# digitalLatchShield.net
KiCad netlist of a schematic drawn in EAGLE
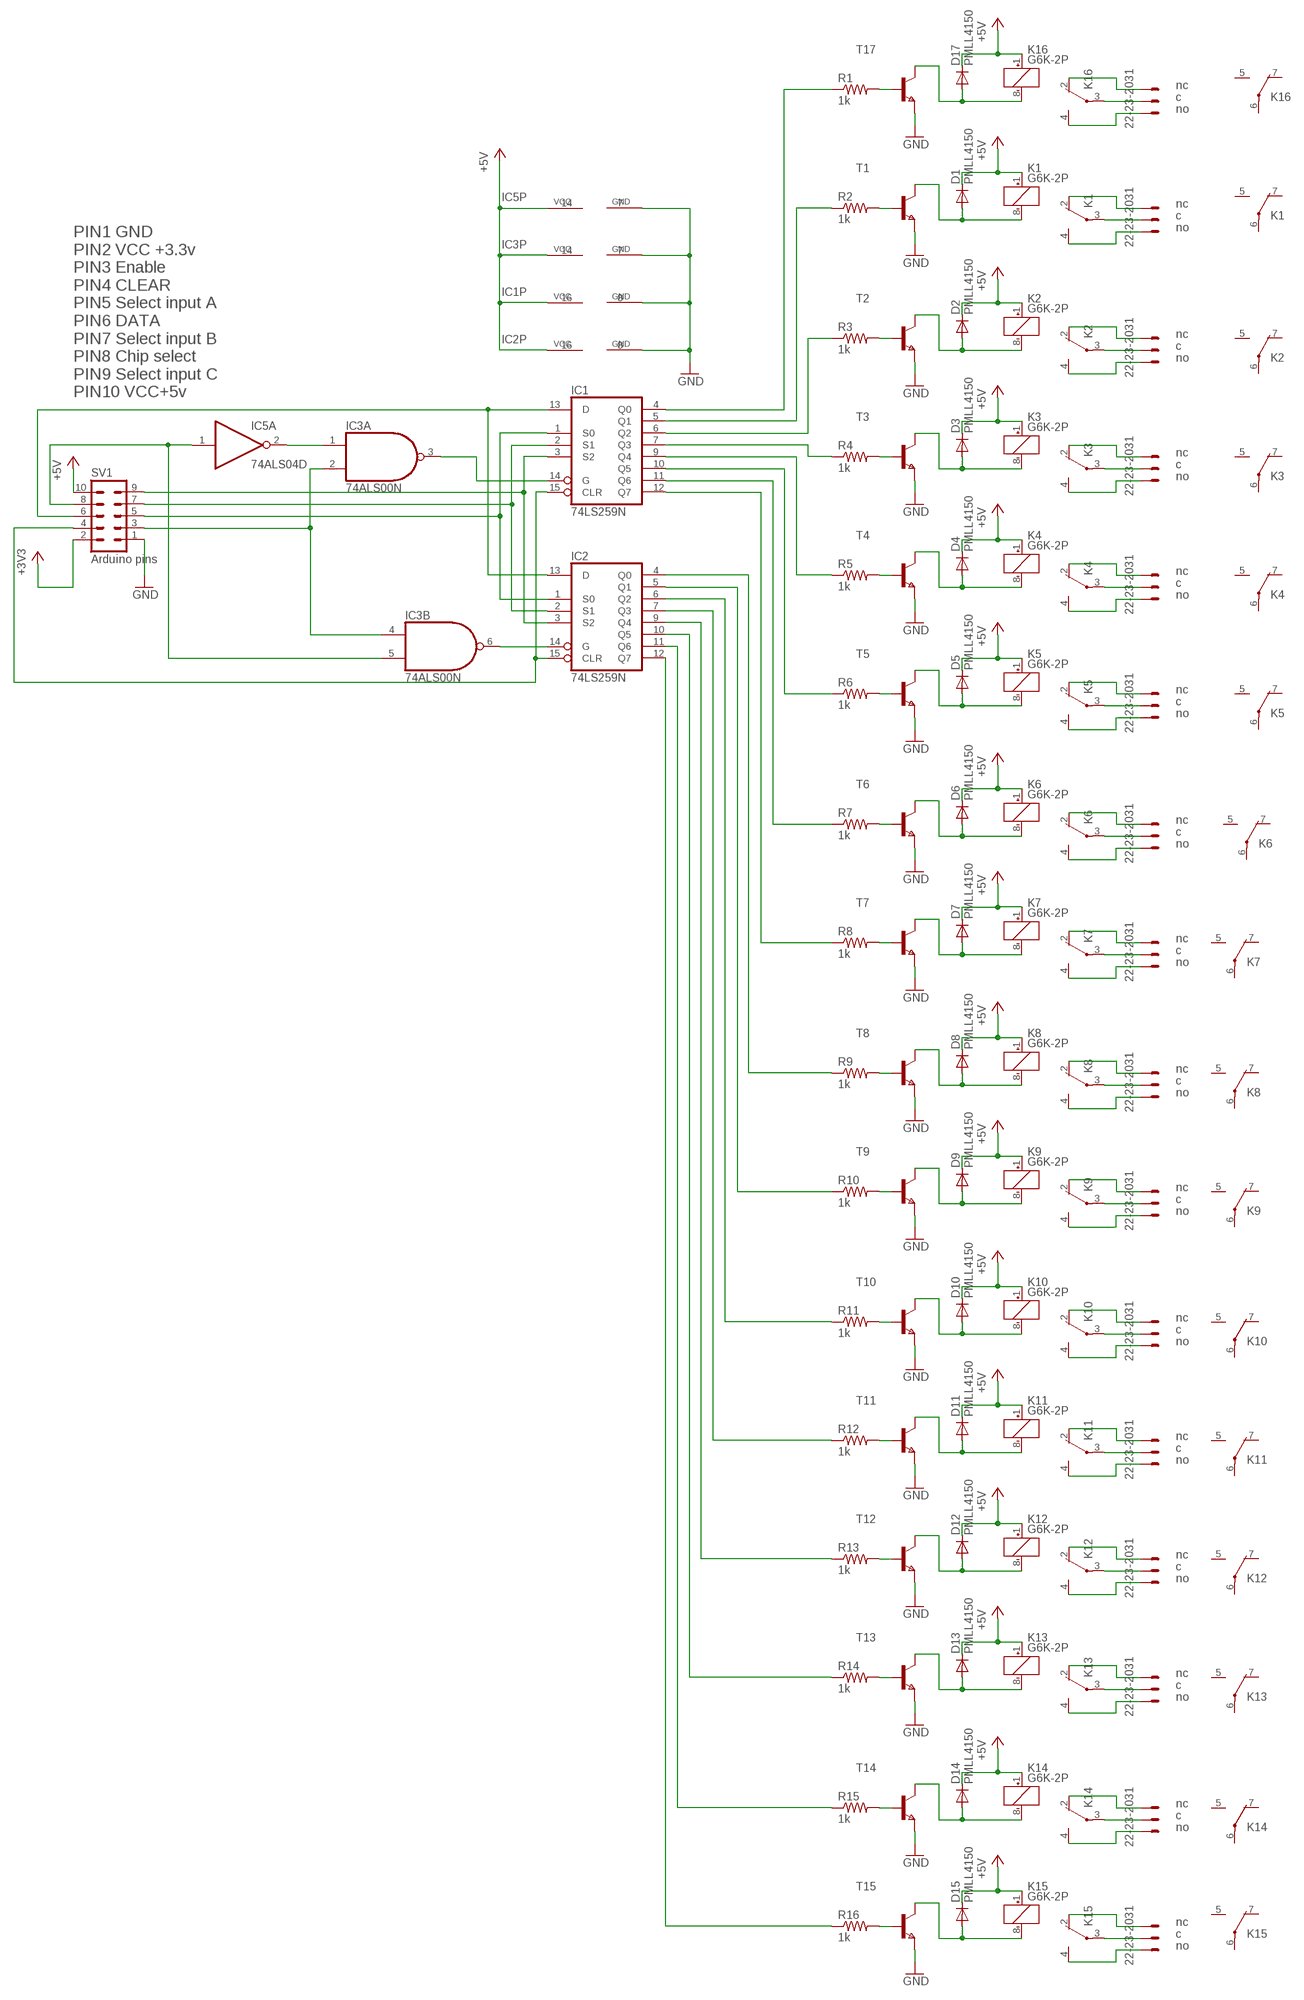
[diagram p0: schematic, sheet 1]

(export (version "E")
  (design (tool "Eeschema 10.0.6"))
  (components
    (comp (ref "D1")
      (value "PMLL4150")
      (footprint "eagle-import:SOD80C")
      (libsource (lib "eagle-import") (part "PMLL4150"))
    )
    (comp (ref "D2")
      (value "PMLL4150")
      (footprint "eagle-import:SOD80C")
      (libsource (lib "eagle-import") (part "PMLL4150"))
    )
    (comp (ref "D3")
      (value "PMLL4150")
      (footprint "eagle-import:SOD80C")
      (libsource (lib "eagle-import") (part "PMLL4150"))
    )
    (comp (ref "D4")
      (value "PMLL4150")
      (footprint "eagle-import:SOD80C")
      (libsource (lib "eagle-import") (part "PMLL4150"))
    )
    (comp (ref "D5")
      (value "PMLL4150")
      (footprint "eagle-import:SOD80C")
      (libsource (lib "eagle-import") (part "PMLL4150"))
    )
    (comp (ref "D6")
      (value "PMLL4150")
      (footprint "eagle-import:SOD80C")
      (libsource (lib "eagle-import") (part "PMLL4150"))
    )
    (comp (ref "D7")
      (value "PMLL4150")
      (footprint "eagle-import:SOD80C")
      (libsource (lib "eagle-import") (part "PMLL4150"))
    )
    (comp (ref "D8")
      (value "PMLL4150")
      (footprint "eagle-import:SOD80C")
      (libsource (lib "eagle-import") (part "PMLL4150"))
    )
    (comp (ref "D9")
      (value "PMLL4150")
      (footprint "eagle-import:SOD80C")
      (libsource (lib "eagle-import") (part "PMLL4150"))
    )
    (comp (ref "D10")
      (value "PMLL4150")
      (footprint "eagle-import:SOD80C")
      (libsource (lib "eagle-import") (part "PMLL4150"))
    )
    (comp (ref "D11")
      (value "PMLL4150")
      (footprint "eagle-import:SOD80C")
      (libsource (lib "eagle-import") (part "PMLL4150"))
    )
    (comp (ref "D12")
      (value "PMLL4150")
      (footprint "eagle-import:SOD80C")
      (libsource (lib "eagle-import") (part "PMLL4150"))
    )
    (comp (ref "D13")
      (value "PMLL4150")
      (footprint "eagle-import:SOD80C")
      (libsource (lib "eagle-import") (part "PMLL4150"))
    )
    (comp (ref "D14")
      (value "PMLL4150")
      (footprint "eagle-import:SOD80C")
      (libsource (lib "eagle-import") (part "PMLL4150"))
    )
    (comp (ref "D15")
      (value "PMLL4150")
      (footprint "eagle-import:SOD80C")
      (libsource (lib "eagle-import") (part "PMLL4150"))
    )
    (comp (ref "D17")
      (value "PMLL4150")
      (footprint "eagle-import:SOD80C")
      (libsource (lib "eagle-import") (part "PMLL4150"))
    )
    (comp (ref "IC1")
      (value "74LS259N")
      (footprint "eagle-import:DIL16")
      (libsource (lib "eagle-import") (part "74259NLS"))
    )
    (comp (ref "IC2")
      (value "74LS259N")
      (footprint "eagle-import:DIL16")
      (libsource (lib "eagle-import") (part "74259NLS"))
    )
    (comp (ref "IC3")
      (value "74ALS00N")
      (footprint "eagle-import:DIL14")
      (libsource (lib "eagle-import") (part "7400NALS"))
    )
    (comp (ref "IC5")
      (value "74ALS04D")
      (footprint "eagle-import:SO14")
      (libsource (lib "eagle-import") (part "7404DALS"))
    )
    (comp (ref "K1")
      (value "G6K-2P")
      (footprint "eagle-import:G6K-2P")
      (fields (field (name "MF") "OMRON COMPONENTS USA") (field (name "MPN") "G6K-2P DC3"))
      (libsource (lib "eagle-import") (part "G6K-2P"))
    )
    (comp (ref "K2")
      (value "G6K-2P")
      (footprint "eagle-import:G6K-2P")
      (fields (field (name "MF") "OMRON COMPONENTS USA") (field (name "MPN") "G6K-2P DC3"))
      (libsource (lib "eagle-import") (part "G6K-2P"))
    )
    (comp (ref "K3")
      (value "G6K-2P")
      (footprint "eagle-import:G6K-2P")
      (fields (field (name "MF") "OMRON COMPONENTS USA") (field (name "MPN") "G6K-2P DC3"))
      (libsource (lib "eagle-import") (part "G6K-2P"))
    )
    (comp (ref "K4")
      (value "G6K-2P")
      (footprint "eagle-import:G6K-2P")
      (fields (field (name "MF") "OMRON COMPONENTS USA") (field (name "MPN") "G6K-2P DC3"))
      (libsource (lib "eagle-import") (part "G6K-2P"))
    )
    (comp (ref "K5")
      (value "G6K-2P")
      (footprint "eagle-import:G6K-2P")
      (fields (field (name "MF") "OMRON COMPONENTS USA") (field (name "MPN") "G6K-2P DC3"))
      (libsource (lib "eagle-import") (part "G6K-2P"))
    )
    (comp (ref "K6")
      (value "G6K-2P")
      (footprint "eagle-import:G6K-2P")
      (fields (field (name "MF") "OMRON COMPONENTS USA") (field (name "MPN") "G6K-2P DC3"))
      (libsource (lib "eagle-import") (part "G6K-2P"))
    )
    (comp (ref "K7")
      (value "G6K-2P")
      (footprint "eagle-import:G6K-2P")
      (fields (field (name "MF") "OMRON COMPONENTS USA") (field (name "MPN") "G6K-2P DC3"))
      (libsource (lib "eagle-import") (part "G6K-2P"))
    )
    (comp (ref "K8")
      (value "G6K-2P")
      (footprint "eagle-import:G6K-2P")
      (fields (field (name "MF") "OMRON COMPONENTS USA") (field (name "MPN") "G6K-2P DC3"))
      (libsource (lib "eagle-import") (part "G6K-2P"))
    )
    (comp (ref "K9")
      (value "G6K-2P")
      (footprint "eagle-import:G6K-2P")
      (fields (field (name "MF") "OMRON COMPONENTS USA") (field (name "MPN") "G6K-2P DC3"))
      (libsource (lib "eagle-import") (part "G6K-2P"))
    )
    (comp (ref "K10")
      (value "G6K-2P")
      (footprint "eagle-import:G6K-2P")
      (fields (field (name "MF") "OMRON COMPONENTS USA") (field (name "MPN") "G6K-2P DC3"))
      (libsource (lib "eagle-import") (part "G6K-2P"))
    )
    (comp (ref "K11")
      (value "G6K-2P")
      (footprint "eagle-import:G6K-2P")
      (fields (field (name "MF") "OMRON COMPONENTS USA") (field (name "MPN") "G6K-2P DC3"))
      (libsource (lib "eagle-import") (part "G6K-2P"))
    )
    (comp (ref "K12")
      (value "G6K-2P")
      (footprint "eagle-import:G6K-2P")
      (fields (field (name "MF") "OMRON COMPONENTS USA") (field (name "MPN") "G6K-2P DC3"))
      (libsource (lib "eagle-import") (part "G6K-2P"))
    )
    (comp (ref "K13")
      (value "G6K-2P")
      (footprint "eagle-import:G6K-2P")
      (fields (field (name "MF") "OMRON COMPONENTS USA") (field (name "MPN") "G6K-2P DC3"))
      (libsource (lib "eagle-import") (part "G6K-2P"))
    )
    (comp (ref "K14")
      (value "G6K-2P")
      (footprint "eagle-import:G6K-2P")
      (fields (field (name "MF") "OMRON COMPONENTS USA") (field (name "MPN") "G6K-2P DC3"))
      (libsource (lib "eagle-import") (part "G6K-2P"))
    )
    (comp (ref "K15")
      (value "G6K-2P")
      (footprint "eagle-import:G6K-2P")
      (fields (field (name "MF") "OMRON COMPONENTS USA") (field (name "MPN") "G6K-2P DC3"))
      (libsource (lib "eagle-import") (part "G6K-2P"))
    )
    (comp (ref "K16")
      (value "G6K-2P")
      (footprint "eagle-import:G6K-2P")
      (fields (field (name "MF") "OMRON COMPONENTS USA") (field (name "MPN") "G6K-2P DC3"))
      (libsource (lib "eagle-import") (part "G6K-2P"))
    )
    (comp (ref "R1")
      (value "1k")
      (footprint "eagle-import:M0805")
      (libsource (lib "eagle-import") (part "R-US_M0805"))
    )
    (comp (ref "R2")
      (value "1k")
      (footprint "eagle-import:M0805")
      (libsource (lib "eagle-import") (part "R-US_M0805"))
    )
    (comp (ref "R3")
      (value "1k")
      (footprint "eagle-import:M0805")
      (libsource (lib "eagle-import") (part "R-US_M0805"))
    )
    (comp (ref "R4")
      (value "1k")
      (footprint "eagle-import:M0805")
      (libsource (lib "eagle-import") (part "R-US_M0805"))
    )
    (comp (ref "R5")
      (value "1k")
      (footprint "eagle-import:M0805")
      (libsource (lib "eagle-import") (part "R-US_M0805"))
    )
    (comp (ref "R6")
      (value "1k")
      (footprint "eagle-import:M0805")
      (libsource (lib "eagle-import") (part "R-US_M0805"))
    )
    (comp (ref "R7")
      (value "1k")
      (footprint "eagle-import:M0805")
      (libsource (lib "eagle-import") (part "R-US_M0805"))
    )
    (comp (ref "R8")
      (value "1k")
      (footprint "eagle-import:M0805")
      (libsource (lib "eagle-import") (part "R-US_M0805"))
    )
    (comp (ref "R9")
      (value "1k")
      (footprint "eagle-import:M0805")
      (libsource (lib "eagle-import") (part "R-US_M0805"))
    )
    (comp (ref "R10")
      (value "1k")
      (footprint "eagle-import:M0805")
      (libsource (lib "eagle-import") (part "R-US_M0805"))
    )
    (comp (ref "R11")
      (value "1k")
      (footprint "eagle-import:M0805")
      (libsource (lib "eagle-import") (part "R-US_M0805"))
    )
    (comp (ref "R12")
      (value "1k")
      (footprint "eagle-import:M0805")
      (libsource (lib "eagle-import") (part "R-US_M0805"))
    )
    (comp (ref "R13")
      (value "1k")
      (footprint "eagle-import:M0805")
      (libsource (lib "eagle-import") (part "R-US_M0805"))
    )
    (comp (ref "R14")
      (value "1k")
      (footprint "eagle-import:M0805")
      (libsource (lib "eagle-import") (part "R-US_M0805"))
    )
    (comp (ref "R15")
      (value "1k")
      (footprint "eagle-import:M0805")
      (libsource (lib "eagle-import") (part "R-US_M0805"))
    )
    (comp (ref "R16")
      (value "1k")
      (footprint "eagle-import:M0805")
      (libsource (lib "eagle-import") (part "R-US_M0805"))
    )
    (comp (ref "SV1")
      (value "Arduino pins")
      (footprint "eagle-import:MA05-2")
      (libsource (lib "eagle-import") (part "MA05-2"))
    )
    (comp (ref "T1")
      (value "NPNSOT23")
      (footprint "eagle-import:SOT-23")
      (fields (field (name "MPN") "DSS20201L-7"))
      (libsource (lib "eagle-import") (part "NPNSOT23"))
    )
    (comp (ref "T2")
      (value "NPNSOT23")
      (footprint "eagle-import:SOT-23")
      (fields (field (name "MPN") "DSS20201L-7"))
      (libsource (lib "eagle-import") (part "NPNSOT23"))
    )
    (comp (ref "T3")
      (value "NPNSOT23")
      (footprint "eagle-import:SOT-23")
      (fields (field (name "MPN") "DSS20201L-7"))
      (libsource (lib "eagle-import") (part "NPNSOT23"))
    )
    (comp (ref "T4")
      (value "NPNSOT23")
      (footprint "eagle-import:SOT-23")
      (fields (field (name "MPN") "DSS20201L-7"))
      (libsource (lib "eagle-import") (part "NPNSOT23"))
    )
    (comp (ref "T5")
      (value "NPNSOT23")
      (footprint "eagle-import:SOT-23")
      (fields (field (name "MPN") "DSS20201L-7"))
      (libsource (lib "eagle-import") (part "NPNSOT23"))
    )
    (comp (ref "T6")
      (value "NPNSOT23")
      (footprint "eagle-import:SOT-23")
      (fields (field (name "MPN") "DSS20201L-7"))
      (libsource (lib "eagle-import") (part "NPNSOT23"))
    )
    (comp (ref "T7")
      (value "NPNSOT23")
      (footprint "eagle-import:SOT-23")
      (fields (field (name "MPN") "DSS20201L-7"))
      (libsource (lib "eagle-import") (part "NPNSOT23"))
    )
    (comp (ref "T8")
      (value "NPNSOT23")
      (footprint "eagle-import:SOT-23")
      (fields (field (name "MPN") "DSS20201L-7"))
      (libsource (lib "eagle-import") (part "NPNSOT23"))
    )
    (comp (ref "T9")
      (value "NPNSOT23")
      (footprint "eagle-import:SOT-23")
      (fields (field (name "MPN") "DSS20201L-7"))
      (libsource (lib "eagle-import") (part "NPNSOT23"))
    )
    (comp (ref "T10")
      (value "NPNSOT23")
      (footprint "eagle-import:SOT-23")
      (fields (field (name "MPN") "DSS20201L-7"))
      (libsource (lib "eagle-import") (part "NPNSOT23"))
    )
    (comp (ref "T11")
      (value "NPNSOT23")
      (footprint "eagle-import:SOT-23")
      (fields (field (name "MPN") "DSS20201L-7"))
      (libsource (lib "eagle-import") (part "NPNSOT23"))
    )
    (comp (ref "T12")
      (value "NPNSOT23")
      (footprint "eagle-import:SOT-23")
      (fields (field (name "MPN") "DSS20201L-7"))
      (libsource (lib "eagle-import") (part "NPNSOT23"))
    )
    (comp (ref "T13")
      (value "NPNSOT23")
      (footprint "eagle-import:SOT-23")
      (fields (field (name "MPN") "DSS20201L-7"))
      (libsource (lib "eagle-import") (part "NPNSOT23"))
    )
    (comp (ref "T14")
      (value "NPNSOT23")
      (footprint "eagle-import:SOT-23")
      (fields (field (name "MPN") "DSS20201L-7"))
      (libsource (lib "eagle-import") (part "NPNSOT23"))
    )
    (comp (ref "T15")
      (value "NPNSOT23")
      (footprint "eagle-import:SOT-23")
      (fields (field (name "MPN") "DSS20201L-7"))
      (libsource (lib "eagle-import") (part "NPNSOT23"))
    )
    (comp (ref "T17")
      (value "NPNSOT23")
      (footprint "eagle-import:SOT-23")
      (fields (field (name "MPN") "DSS20201L-7"))
      (libsource (lib "eagle-import") (part "NPNSOT23"))
    )
    (comp (ref "X1")
      (value "22-23-2031")
      (footprint "eagle-import:22-23-2031")
      (fields (field (name "MF") "MOLEX"))
      (libsource (lib "eagle-import") (part "22-23-2031"))
    )
    (comp (ref "X2")
      (value "22-23-2031")
      (footprint "eagle-import:22-23-2031")
      (fields (field (name "MF") "MOLEX"))
      (libsource (lib "eagle-import") (part "22-23-2031"))
    )
    (comp (ref "X3")
      (value "22-23-2031")
      (footprint "eagle-import:22-23-2031")
      (fields (field (name "MF") "MOLEX"))
      (libsource (lib "eagle-import") (part "22-23-2031"))
    )
    (comp (ref "X4")
      (value "22-23-2031")
      (footprint "eagle-import:22-23-2031")
      (fields (field (name "MF") "MOLEX"))
      (libsource (lib "eagle-import") (part "22-23-2031"))
    )
    (comp (ref "X5")
      (value "22-23-2031")
      (footprint "eagle-import:22-23-2031")
      (fields (field (name "MF") "MOLEX"))
      (libsource (lib "eagle-import") (part "22-23-2031"))
    )
    (comp (ref "X6")
      (value "22-23-2031")
      (footprint "eagle-import:22-23-2031")
      (fields (field (name "MF") "MOLEX"))
      (libsource (lib "eagle-import") (part "22-23-2031"))
    )
    (comp (ref "X7")
      (value "22-23-2031")
      (footprint "eagle-import:22-23-2031")
      (fields (field (name "MF") "MOLEX"))
      (libsource (lib "eagle-import") (part "22-23-2031"))
    )
    (comp (ref "X8")
      (value "22-23-2031")
      (footprint "eagle-import:22-23-2031")
      (fields (field (name "MF") "MOLEX"))
      (libsource (lib "eagle-import") (part "22-23-2031"))
    )
    (comp (ref "X9")
      (value "22-23-2031")
      (footprint "eagle-import:22-23-2031")
      (fields (field (name "MF") "MOLEX"))
      (libsource (lib "eagle-import") (part "22-23-2031"))
    )
    (comp (ref "X10")
      (value "22-23-2031")
      (footprint "eagle-import:22-23-2031")
      (fields (field (name "MF") "MOLEX"))
      (libsource (lib "eagle-import") (part "22-23-2031"))
    )
    (comp (ref "X11")
      (value "22-23-2031")
      (footprint "eagle-import:22-23-2031")
      (fields (field (name "MF") "MOLEX"))
      (libsource (lib "eagle-import") (part "22-23-2031"))
    )
    (comp (ref "X12")
      (value "22-23-2031")
      (footprint "eagle-import:22-23-2031")
      (fields (field (name "MF") "MOLEX"))
      (libsource (lib "eagle-import") (part "22-23-2031"))
    )
    (comp (ref "X13")
      (value "22-23-2031")
      (footprint "eagle-import:22-23-2031")
      (fields (field (name "MF") "MOLEX"))
      (libsource (lib "eagle-import") (part "22-23-2031"))
    )
    (comp (ref "X14")
      (value "22-23-2031")
      (footprint "eagle-import:22-23-2031")
      (fields (field (name "MF") "MOLEX"))
      (libsource (lib "eagle-import") (part "22-23-2031"))
    )
    (comp (ref "X15")
      (value "22-23-2031")
      (footprint "eagle-import:22-23-2031")
      (fields (field (name "MF") "MOLEX"))
      (libsource (lib "eagle-import") (part "22-23-2031"))
    )
    (comp (ref "X16")
      (value "22-23-2031")
      (footprint "eagle-import:22-23-2031")
      (fields (field (name "MF") "MOLEX"))
      (libsource (lib "eagle-import") (part "22-23-2031"))
    )
  )
  (nets
    (net (code "1") (name "+3V3") (class "Default")
      (node (ref "SV1") (pin "2") (pinfunction "2_2") (pintype "passive"))
    )
    (net (code "2") (name "+5V") (class "Default")
      (node (ref "D1") (pin "C") (pinfunction "C_C") (pintype "passive"))
      (node (ref "D10") (pin "C") (pinfunction "C_C") (pintype "passive"))
      (node (ref "D11") (pin "C") (pinfunction "C_C") (pintype "passive"))
      (node (ref "D12") (pin "C") (pinfunction "C_C") (pintype "passive"))
      (node (ref "D13") (pin "C") (pinfunction "C_C") (pintype "passive"))
      (node (ref "D14") (pin "C") (pinfunction "C_C") (pintype "passive"))
      (node (ref "D15") (pin "C") (pinfunction "C_C") (pintype "passive"))
      (node (ref "D17") (pin "C") (pinfunction "C_C") (pintype "passive"))
      (node (ref "D2") (pin "C") (pinfunction "C_C") (pintype "passive"))
      (node (ref "D3") (pin "C") (pinfunction "C_C") (pintype "passive"))
      (node (ref "D4") (pin "C") (pinfunction "C_C") (pintype "passive"))
      (node (ref "D5") (pin "C") (pinfunction "C_C") (pintype "passive"))
      (node (ref "D6") (pin "C") (pinfunction "C_C") (pintype "passive"))
      (node (ref "D7") (pin "C") (pinfunction "C_C") (pintype "passive"))
      (node (ref "D8") (pin "C") (pinfunction "C_C") (pintype "passive"))
      (node (ref "D9") (pin "C") (pinfunction "C_C") (pintype "passive"))
      (node (ref "IC1") (pin "16") (pinfunction "VCC_16") (pintype "power_in"))
      (node (ref "IC2") (pin "16") (pinfunction "VCC_16") (pintype "power_in"))
      (node (ref "IC3") (pin "14") (pinfunction "VCC_14") (pintype "power_in"))
      (node (ref "IC5") (pin "14") (pinfunction "VCC_14") (pintype "power_in"))
      (node (ref "K1") (pin "1") (pinfunction "+_1") (pintype "passive"))
      (node (ref "K10") (pin "1") (pinfunction "+_1") (pintype "passive"))
      (node (ref "K11") (pin "1") (pinfunction "+_1") (pintype "passive"))
      (node (ref "K12") (pin "1") (pinfunction "+_1") (pintype "passive"))
      (node (ref "K13") (pin "1") (pinfunction "+_1") (pintype "passive"))
      (node (ref "K14") (pin "1") (pinfunction "+_1") (pintype "passive"))
      (node (ref "K15") (pin "1") (pinfunction "+_1") (pintype "passive"))
      (node (ref "K16") (pin "1") (pinfunction "+_1") (pintype "passive"))
      (node (ref "K2") (pin "1") (pinfunction "+_1") (pintype "passive"))
      (node (ref "K3") (pin "1") (pinfunction "+_1") (pintype "passive"))
      (node (ref "K4") (pin "1") (pinfunction "+_1") (pintype "passive"))
      (node (ref "K5") (pin "1") (pinfunction "+_1") (pintype "passive"))
      (node (ref "K6") (pin "1") (pinfunction "+_1") (pintype "passive"))
      (node (ref "K7") (pin "1") (pinfunction "+_1") (pintype "passive"))
      (node (ref "K8") (pin "1") (pinfunction "+_1") (pintype "passive"))
      (node (ref "K9") (pin "1") (pinfunction "+_1") (pintype "passive"))
      (node (ref "SV1") (pin "10") (pinfunction "10_10") (pintype "passive"))
    )
    (net (code "3") (name "GND") (class "Default")
      (node (ref "IC1") (pin "8") (pinfunction "GND_8") (pintype "power_in"))
      (node (ref "IC2") (pin "8") (pinfunction "GND_8") (pintype "power_in"))
      (node (ref "IC3") (pin "7") (pinfunction "GND_7") (pintype "power_in"))
      (node (ref "IC5") (pin "7") (pinfunction "GND_7") (pintype "power_in"))
      (node (ref "SV1") (pin "1") (pinfunction "1_1") (pintype "passive"))
      (node (ref "T1") (pin "2") (pinfunction "E_2") (pintype "passive"))
      (node (ref "T10") (pin "2") (pinfunction "E_2") (pintype "passive"))
      (node (ref "T11") (pin "2") (pinfunction "E_2") (pintype "passive"))
      (node (ref "T12") (pin "2") (pinfunction "E_2") (pintype "passive"))
      (node (ref "T13") (pin "2") (pinfunction "E_2") (pintype "passive"))
      (node (ref "T14") (pin "2") (pinfunction "E_2") (pintype "passive"))
      (node (ref "T15") (pin "2") (pinfunction "E_2") (pintype "passive"))
      (node (ref "T17") (pin "2") (pinfunction "E_2") (pintype "passive"))
      (node (ref "T2") (pin "2") (pinfunction "E_2") (pintype "passive"))
      (node (ref "T3") (pin "2") (pinfunction "E_2") (pintype "passive"))
      (node (ref "T4") (pin "2") (pinfunction "E_2") (pintype "passive"))
      (node (ref "T5") (pin "2") (pinfunction "E_2") (pintype "passive"))
      (node (ref "T6") (pin "2") (pinfunction "E_2") (pintype "passive"))
      (node (ref "T7") (pin "2") (pinfunction "E_2") (pintype "passive"))
      (node (ref "T8") (pin "2") (pinfunction "E_2") (pintype "passive"))
      (node (ref "T9") (pin "2") (pinfunction "E_2") (pintype "passive"))
    )
    (net (code "4") (name "Net-(IC1A-CLR)") (class "Default")
      (node (ref "IC1") (pin "15") (pinfunction "CLR_15") (pintype "input"))
      (node (ref "IC2") (pin "15") (pinfunction "CLR_15") (pintype "input"))
      (node (ref "SV1") (pin "4") (pinfunction "4_4") (pintype "passive"))
    )
    (net (code "5") (name "Net-(IC1A-D)") (class "Default")
      (node (ref "IC1") (pin "13") (pinfunction "D_13") (pintype "input"))
      (node (ref "IC2") (pin "13") (pinfunction "D_13") (pintype "input"))
      (node (ref "SV1") (pin "6") (pinfunction "6_6") (pintype "passive"))
    )
    (net (code "6") (name "Net-(IC1A-G)") (class "Default")
      (node (ref "IC1") (pin "14") (pinfunction "G_14") (pintype "input"))
      (node (ref "IC3") (pin "3") (pinfunction "O_3") (pintype "output"))
    )
    (net (code "7") (name "Net-(IC1A-Q0)") (class "Default")
      (node (ref "IC1") (pin "4") (pinfunction "Q0_4") (pintype "output"))
      (node (ref "R1") (pin "1") (pinfunction "1_1") (pintype "passive"))
    )
    (net (code "8") (name "Net-(IC1A-Q1)") (class "Default")
      (node (ref "IC1") (pin "5") (pinfunction "Q1_5") (pintype "output"))
      (node (ref "R2") (pin "1") (pinfunction "1_1") (pintype "passive"))
    )
    (net (code "9") (name "Net-(IC1A-Q2)") (class "Default")
      (node (ref "IC1") (pin "6") (pinfunction "Q2_6") (pintype "output"))
      (node (ref "R3") (pin "1") (pinfunction "1_1") (pintype "passive"))
    )
    (net (code "10") (name "Net-(IC1A-Q3)") (class "Default")
      (node (ref "IC1") (pin "7") (pinfunction "Q3_7") (pintype "output"))
      (node (ref "R4") (pin "1") (pinfunction "1_1") (pintype "passive"))
    )
    (net (code "11") (name "Net-(IC1A-Q4)") (class "Default")
      (node (ref "IC1") (pin "9") (pinfunction "Q4_9") (pintype "output"))
      (node (ref "R5") (pin "1") (pinfunction "1_1") (pintype "passive"))
    )
    (net (code "12") (name "Net-(IC1A-Q5)") (class "Default")
      (node (ref "IC1") (pin "10") (pinfunction "Q5_10") (pintype "output"))
      (node (ref "R6") (pin "1") (pinfunction "1_1") (pintype "passive"))
    )
    (net (code "13") (name "Net-(IC1A-Q6)") (class "Default")
      (node (ref "IC1") (pin "11") (pinfunction "Q6_11") (pintype "output"))
      (node (ref "R7") (pin "1") (pinfunction "1_1") (pintype "passive"))
    )
    (net (code "14") (name "Net-(IC1A-Q7)") (class "Default")
      (node (ref "IC1") (pin "12") (pinfunction "Q7_12") (pintype "output"))
      (node (ref "R8") (pin "1") (pinfunction "1_1") (pintype "passive"))
    )
    (net (code "15") (name "Net-(IC1A-S0)") (class "Default")
      (node (ref "IC1") (pin "1") (pinfunction "S0_1") (pintype "input"))
      (node (ref "IC2") (pin "1") (pinfunction "S0_1") (pintype "input"))
      (node (ref "SV1") (pin "5") (pinfunction "5_5") (pintype "passive"))
    )
    (net (code "16") (name "Net-(IC1A-S1)") (class "Default")
      (node (ref "IC1") (pin "2") (pinfunction "S1_2") (pintype "input"))
      (node (ref "IC2") (pin "2") (pinfunction "S1_2") (pintype "input"))
      (node (ref "SV1") (pin "7") (pinfunction "7_7") (pintype "passive"))
    )
    (net (code "17") (name "Net-(IC1A-S2)") (class "Default")
      (node (ref "IC1") (pin "3") (pinfunction "S2_3") (pintype "input"))
      (node (ref "IC2") (pin "3") (pinfunction "S2_3") (pintype "input"))
      (node (ref "SV1") (pin "9") (pinfunction "9_9") (pintype "passive"))
    )
    (net (code "18") (name "Net-(IC2A-G)") (class "Default")
      (node (ref "IC2") (pin "14") (pinfunction "G_14") (pintype "input"))
      (node (ref "IC3") (pin "6") (pinfunction "O_6") (pintype "output"))
    )
    (net (code "19") (name "Net-(IC2A-Q0)") (class "Default")
      (node (ref "IC2") (pin "4") (pinfunction "Q0_4") (pintype "output"))
      (node (ref "R9") (pin "1") (pinfunction "1_1") (pintype "passive"))
    )
    (net (code "20") (name "Net-(IC2A-Q1)") (class "Default")
      (node (ref "IC2") (pin "5") (pinfunction "Q1_5") (pintype "output"))
      (node (ref "R10") (pin "1") (pinfunction "1_1") (pintype "passive"))
    )
    (net (code "21") (name "Net-(IC2A-Q2)") (class "Default")
      (node (ref "IC2") (pin "6") (pinfunction "Q2_6") (pintype "output"))
      (node (ref "R11") (pin "1") (pinfunction "1_1") (pintype "passive"))
    )
    (net (code "22") (name "Net-(IC2A-Q3)") (class "Default")
      (node (ref "IC2") (pin "7") (pinfunction "Q3_7") (pintype "output"))
      (node (ref "R12") (pin "1") (pinfunction "1_1") (pintype "passive"))
    )
    (net (code "23") (name "Net-(IC2A-Q4)") (class "Default")
      (node (ref "IC2") (pin "9") (pinfunction "Q4_9") (pintype "output"))
      (node (ref "R13") (pin "1") (pinfunction "1_1") (pintype "passive"))
    )
    (net (code "24") (name "Net-(IC2A-Q5)") (class "Default")
      (node (ref "IC2") (pin "10") (pinfunction "Q5_10") (pintype "output"))
      (node (ref "R14") (pin "1") (pinfunction "1_1") (pintype "passive"))
    )
    (net (code "25") (name "Net-(IC2A-Q6)") (class "Default")
      (node (ref "IC2") (pin "11") (pinfunction "Q6_11") (pintype "output"))
      (node (ref "R15") (pin "1") (pinfunction "1_1") (pintype "passive"))
    )
    (net (code "26") (name "Net-(IC2A-Q7)") (class "Default")
      (node (ref "IC2") (pin "12") (pinfunction "Q7_12") (pintype "output"))
      (node (ref "R16") (pin "1") (pinfunction "1_1") (pintype "passive"))
    )
    (net (code "27") (name "Net-(IC3A-I0)") (class "Default")
      (node (ref "IC3") (pin "1") (pinfunction "I0_1") (pintype "input"))
      (node (ref "IC5") (pin "2") (pinfunction "O_2") (pintype "output"))
    )
    (net (code "28") (name "Net-(IC3A-I1)") (class "Default")
      (node (ref "IC3") (pin "2") (pinfunction "I1_2") (pintype "input"))
      (node (ref "IC3") (pin "4") (pinfunction "I0_4") (pintype "input"))
      (node (ref "SV1") (pin "3") (pinfunction "3_3") (pintype "passive"))
    )
    (net (code "29") (name "Net-(IC3B-I1)") (class "Default")
      (node (ref "IC3") (pin "5") (pinfunction "I1_5") (pintype "input"))
      (node (ref "IC5") (pin "1") (pinfunction "I_1") (pintype "input"))
      (node (ref "SV1") (pin "8") (pinfunction "8_8") (pintype "passive"))
    )
    (net (code "30") (name "Net-(K1A--)") (class "Default")
      (node (ref "D1") (pin "A") (pinfunction "A_A") (pintype "passive"))
      (node (ref "K1") (pin "8") (pinfunction "-_8") (pintype "passive"))
      (node (ref "T1") (pin "1") (pinfunction "C_1") (pintype "passive"))
    )
    (net (code "31") (name "Net-(K1B-O)") (class "Default")
      (node (ref "K1") (pin "2") (pinfunction "O_2") (pintype "passive"))
      (node (ref "X2") (pin "1") (pinfunction "S_1") (pintype "passive"))
    )
    (net (code "32") (name "Net-(K1B-P)") (class "Default")
      (node (ref "K1") (pin "3") (pinfunction "P_3") (pintype "passive"))
      (node (ref "X2") (pin "2") (pinfunction "S_2") (pintype "passive"))
    )
    (net (code "33") (name "Net-(K1B-S)") (class "Default")
      (node (ref "K1") (pin "4") (pinfunction "S_4") (pintype "passive"))
      (node (ref "X2") (pin "3") (pinfunction "S_3") (pintype "passive"))
    )
    (net (code "34") (name "Net-(K2A--)") (class "Default")
      (node (ref "D2") (pin "A") (pinfunction "A_A") (pintype "passive"))
      (node (ref "K2") (pin "8") (pinfunction "-_8") (pintype "passive"))
      (node (ref "T2") (pin "1") (pinfunction "C_1") (pintype "passive"))
    )
    (net (code "35") (name "Net-(K2B-O)") (class "Default")
      (node (ref "K2") (pin "2") (pinfunction "O_2") (pintype "passive"))
      (node (ref "X3") (pin "1") (pinfunction "S_1") (pintype "passive"))
    )
    (net (code "36") (name "Net-(K2B-P)") (class "Default")
      (node (ref "K2") (pin "3") (pinfunction "P_3") (pintype "passive"))
      (node (ref "X3") (pin "2") (pinfunction "S_2") (pintype "passive"))
    )
    (net (code "37") (name "Net-(K2B-S)") (class "Default")
      (node (ref "K2") (pin "4") (pinfunction "S_4") (pintype "passive"))
      (node (ref "X3") (pin "3") (pinfunction "S_3") (pintype "passive"))
    )
    (net (code "38") (name "Net-(K3A--)") (class "Default")
      (node (ref "D3") (pin "A") (pinfunction "A_A") (pintype "passive"))
      (node (ref "K3") (pin "8") (pinfunction "-_8") (pintype "passive"))
      (node (ref "T3") (pin "1") (pinfunction "C_1") (pintype "passive"))
    )
    (net (code "39") (name "Net-(K3B-O)") (class "Default")
      (node (ref "K3") (pin "2") (pinfunction "O_2") (pintype "passive"))
      (node (ref "X4") (pin "1") (pinfunction "S_1") (pintype "passive"))
    )
    (net (code "40") (name "Net-(K3B-P)") (class "Default")
      (node (ref "K3") (pin "3") (pinfunction "P_3") (pintype "passive"))
      (node (ref "X4") (pin "2") (pinfunction "S_2") (pintype "passive"))
    )
    (net (code "41") (name "Net-(K3B-S)") (class "Default")
      (node (ref "K3") (pin "4") (pinfunction "S_4") (pintype "passive"))
      (node (ref "X4") (pin "3") (pinfunction "S_3") (pintype "passive"))
    )
    (net (code "42") (name "Net-(K4A--)") (class "Default")
      (node (ref "D4") (pin "A") (pinfunction "A_A") (pintype "passive"))
      (node (ref "K4") (pin "8") (pinfunction "-_8") (pintype "passive"))
      (node (ref "T4") (pin "1") (pinfunction "C_1") (pintype "passive"))
    )
    (net (code "43") (name "Net-(K4B-O)") (class "Default")
      (node (ref "K4") (pin "2") (pinfunction "O_2") (pintype "passive"))
      (node (ref "X5") (pin "1") (pinfunction "S_1") (pintype "passive"))
    )
    (net (code "44") (name "Net-(K4B-P)") (class "Default")
      (node (ref "K4") (pin "3") (pinfunction "P_3") (pintype "passive"))
      (node (ref "X5") (pin "2") (pinfunction "S_2") (pintype "passive"))
    )
    (net (code "45") (name "Net-(K4B-S)") (class "Default")
      (node (ref "K4") (pin "4") (pinfunction "S_4") (pintype "passive"))
      (node (ref "X5") (pin "3") (pinfunction "S_3") (pintype "passive"))
    )
    (net (code "46") (name "Net-(K5A--)") (class "Default")
      (node (ref "D5") (pin "A") (pinfunction "A_A") (pintype "passive"))
      (node (ref "K5") (pin "8") (pinfunction "-_8") (pintype "passive"))
      (node (ref "T5") (pin "1") (pinfunction "C_1") (pintype "passive"))
    )
    (net (code "47") (name "Net-(K5B-O)") (class "Default")
      (node (ref "K5") (pin "2") (pinfunction "O_2") (pintype "passive"))
      (node (ref "X6") (pin "1") (pinfunction "S_1") (pintype "passive"))
    )
    (net (code "48") (name "Net-(K5B-P)") (class "Default")
      (node (ref "K5") (pin "3") (pinfunction "P_3") (pintype "passive"))
      (node (ref "X6") (pin "2") (pinfunction "S_2") (pintype "passive"))
    )
    (net (code "49") (name "Net-(K5B-S)") (class "Default")
      (node (ref "K5") (pin "4") (pinfunction "S_4") (pintype "passive"))
      (node (ref "X6") (pin "3") (pinfunction "S_3") (pintype "passive"))
    )
    (net (code "50") (name "Net-(K6A--)") (class "Default")
      (node (ref "D6") (pin "A") (pinfunction "A_A") (pintype "passive"))
      (node (ref "K6") (pin "8") (pinfunction "-_8") (pintype "passive"))
      (node (ref "T6") (pin "1") (pinfunction "C_1") (pintype "passive"))
    )
    (net (code "51") (name "Net-(K6B-O)") (class "Default")
      (node (ref "K6") (pin "2") (pinfunction "O_2") (pintype "passive"))
      (node (ref "X7") (pin "1") (pinfunction "S_1") (pintype "passive"))
    )
    (net (code "52") (name "Net-(K6B-P)") (class "Default")
      (node (ref "K6") (pin "3") (pinfunction "P_3") (pintype "passive"))
      (node (ref "X7") (pin "2") (pinfunction "S_2") (pintype "passive"))
    )
    (net (code "53") (name "Net-(K6B-S)") (class "Default")
      (node (ref "K6") (pin "4") (pinfunction "S_4") (pintype "passive"))
      (node (ref "X7") (pin "3") (pinfunction "S_3") (pintype "passive"))
    )
    (net (code "54") (name "Net-(K7A--)") (class "Default")
      (node (ref "D7") (pin "A") (pinfunction "A_A") (pintype "passive"))
      (node (ref "K7") (pin "8") (pinfunction "-_8") (pintype "passive"))
      (node (ref "T7") (pin "1") (pinfunction "C_1") (pintype "passive"))
    )
    (net (code "55") (name "Net-(K7B-O)") (class "Default")
      (node (ref "K7") (pin "2") (pinfunction "O_2") (pintype "passive"))
      (node (ref "X8") (pin "1") (pinfunction "S_1") (pintype "passive"))
    )
    (net (code "56") (name "Net-(K7B-P)") (class "Default")
      (node (ref "K7") (pin "3") (pinfunction "P_3") (pintype "passive"))
      (node (ref "X8") (pin "2") (pinfunction "S_2") (pintype "passive"))
    )
    (net (code "57") (name "Net-(K7B-S)") (class "Default")
      (node (ref "K7") (pin "4") (pinfunction "S_4") (pintype "passive"))
      (node (ref "X8") (pin "3") (pinfunction "S_3") (pintype "passive"))
    )
    (net (code "58") (name "Net-(K8A--)") (class "Default")
      (node (ref "D8") (pin "A") (pinfunction "A_A") (pintype "passive"))
      (node (ref "K8") (pin "8") (pinfunction "-_8") (pintype "passive"))
      (node (ref "T8") (pin "1") (pinfunction "C_1") (pintype "passive"))
    )
    (net (code "59") (name "Net-(K8B-O)") (class "Default")
      (node (ref "K8") (pin "2") (pinfunction "O_2") (pintype "passive"))
      (node (ref "X9") (pin "1") (pinfunction "S_1") (pintype "passive"))
    )
    (net (code "60") (name "Net-(K8B-P)") (class "Default")
      (node (ref "K8") (pin "3") (pinfunction "P_3") (pintype "passive"))
      (node (ref "X9") (pin "2") (pinfunction "S_2") (pintype "passive"))
    )
    (net (code "61") (name "Net-(K8B-S)") (class "Default")
      (node (ref "K8") (pin "4") (pinfunction "S_4") (pintype "passive"))
      (node (ref "X9") (pin "3") (pinfunction "S_3") (pintype "passive"))
    )
    (net (code "62") (name "Net-(K9A--)") (class "Default")
      (node (ref "D9") (pin "A") (pinfunction "A_A") (pintype "passive"))
      (node (ref "K9") (pin "8") (pinfunction "-_8") (pintype "passive"))
      (node (ref "T9") (pin "1") (pinfunction "C_1") (pintype "passive"))
    )
    (net (code "63") (name "Net-(K9B-O)") (class "Default")
      (node (ref "K9") (pin "2") (pinfunction "O_2") (pintype "passive"))
      (node (ref "X10") (pin "1") (pinfunction "S_1") (pintype "passive"))
    )
    (net (code "64") (name "Net-(K9B-P)") (class "Default")
      (node (ref "K9") (pin "3") (pinfunction "P_3") (pintype "passive"))
      (node (ref "X10") (pin "2") (pinfunction "S_2") (pintype "passive"))
    )
    (net (code "65") (name "Net-(K9B-S)") (class "Default")
      (node (ref "K9") (pin "4") (pinfunction "S_4") (pintype "passive"))
      (node (ref "X10") (pin "3") (pinfunction "S_3") (pintype "passive"))
    )
    (net (code "66") (name "Net-(K10A--)") (class "Default")
      (node (ref "D10") (pin "A") (pinfunction "A_A") (pintype "passive"))
      (node (ref "K10") (pin "8") (pinfunction "-_8") (pintype "passive"))
      (node (ref "T10") (pin "1") (pinfunction "C_1") (pintype "passive"))
    )
    (net (code "67") (name "Net-(K10B-O)") (class "Default")
      (node (ref "K10") (pin "2") (pinfunction "O_2") (pintype "passive"))
      (node (ref "X11") (pin "1") (pinfunction "S_1") (pintype "passive"))
    )
    (net (code "68") (name "Net-(K10B-P)") (class "Default")
      (node (ref "K10") (pin "3") (pinfunction "P_3") (pintype "passive"))
      (node (ref "X11") (pin "2") (pinfunction "S_2") (pintype "passive"))
    )
    (net (code "69") (name "Net-(K10B-S)") (class "Default")
      (node (ref "K10") (pin "4") (pinfunction "S_4") (pintype "passive"))
      (node (ref "X11") (pin "3") (pinfunction "S_3") (pintype "passive"))
    )
    (net (code "70") (name "Net-(K11A--)") (class "Default")
      (node (ref "D11") (pin "A") (pinfunction "A_A") (pintype "passive"))
      (node (ref "K11") (pin "8") (pinfunction "-_8") (pintype "passive"))
      (node (ref "T11") (pin "1") (pinfunction "C_1") (pintype "passive"))
    )
    (net (code "71") (name "Net-(K11B-O)") (class "Default")
      (node (ref "K11") (pin "2") (pinfunction "O_2") (pintype "passive"))
      (node (ref "X12") (pin "1") (pinfunction "S_1") (pintype "passive"))
    )
    (net (code "72") (name "Net-(K11B-P)") (class "Default")
      (node (ref "K11") (pin "3") (pinfunction "P_3") (pintype "passive"))
      (node (ref "X12") (pin "2") (pinfunction "S_2") (pintype "passive"))
    )
    (net (code "73") (name "Net-(K11B-S)") (class "Default")
      (node (ref "K11") (pin "4") (pinfunction "S_4") (pintype "passive"))
      (node (ref "X12") (pin "3") (pinfunction "S_3") (pintype "passive"))
    )
    (net (code "74") (name "Net-(K12A--)") (class "Default")
      (node (ref "D12") (pin "A") (pinfunction "A_A") (pintype "passive"))
      (node (ref "K12") (pin "8") (pinfunction "-_8") (pintype "passive"))
      (node (ref "T12") (pin "1") (pinfunction "C_1") (pintype "passive"))
    )
    (net (code "75") (name "Net-(K12B-O)") (class "Default")
      (node (ref "K12") (pin "2") (pinfunction "O_2") (pintype "passive"))
      (node (ref "X13") (pin "1") (pinfunction "S_1") (pintype "passive"))
    )
    (net (code "76") (name "Net-(K12B-P)") (class "Default")
      (node (ref "K12") (pin "3") (pinfunction "P_3") (pintype "passive"))
      (node (ref "X13") (pin "2") (pinfunction "S_2") (pintype "passive"))
    )
    (net (code "77") (name "Net-(K12B-S)") (class "Default")
      (node (ref "K12") (pin "4") (pinfunction "S_4") (pintype "passive"))
      (node (ref "X13") (pin "3") (pinfunction "S_3") (pintype "passive"))
    )
    (net (code "78") (name "Net-(K13A--)") (class "Default")
      (node (ref "D13") (pin "A") (pinfunction "A_A") (pintype "passive"))
      (node (ref "K13") (pin "8") (pinfunction "-_8") (pintype "passive"))
      (node (ref "T13") (pin "1") (pinfunction "C_1") (pintype "passive"))
    )
    (net (code "79") (name "Net-(K13B-O)") (class "Default")
      (node (ref "K13") (pin "2") (pinfunction "O_2") (pintype "passive"))
      (node (ref "X14") (pin "1") (pinfunction "S_1") (pintype "passive"))
    )
    (net (code "80") (name "Net-(K13B-P)") (class "Default")
      (node (ref "K13") (pin "3") (pinfunction "P_3") (pintype "passive"))
      (node (ref "X14") (pin "2") (pinfunction "S_2") (pintype "passive"))
    )
    (net (code "81") (name "Net-(K13B-S)") (class "Default")
      (node (ref "K13") (pin "4") (pinfunction "S_4") (pintype "passive"))
      (node (ref "X14") (pin "3") (pinfunction "S_3") (pintype "passive"))
    )
    (net (code "82") (name "Net-(K14A--)") (class "Default")
      (node (ref "D14") (pin "A") (pinfunction "A_A") (pintype "passive"))
      (node (ref "K14") (pin "8") (pinfunction "-_8") (pintype "passive"))
      (node (ref "T14") (pin "1") (pinfunction "C_1") (pintype "passive"))
    )
    (net (code "83") (name "Net-(K14B-O)") (class "Default")
      (node (ref "K14") (pin "2") (pinfunction "O_2") (pintype "passive"))
      (node (ref "X15") (pin "1") (pinfunction "S_1") (pintype "passive"))
    )
    (net (code "84") (name "Net-(K14B-P)") (class "Default")
      (node (ref "K14") (pin "3") (pinfunction "P_3") (pintype "passive"))
      (node (ref "X15") (pin "2") (pinfunction "S_2") (pintype "passive"))
    )
    (net (code "85") (name "Net-(K14B-S)") (class "Default")
      (node (ref "K14") (pin "4") (pinfunction "S_4") (pintype "passive"))
      (node (ref "X15") (pin "3") (pinfunction "S_3") (pintype "passive"))
    )
    (net (code "86") (name "Net-(K15A--)") (class "Default")
      (node (ref "D15") (pin "A") (pinfunction "A_A") (pintype "passive"))
      (node (ref "K15") (pin "8") (pinfunction "-_8") (pintype "passive"))
      (node (ref "T15") (pin "1") (pinfunction "C_1") (pintype "passive"))
    )
    (net (code "87") (name "Net-(K15B-O)") (class "Default")
      (node (ref "K15") (pin "2") (pinfunction "O_2") (pintype "passive"))
      (node (ref "X16") (pin "1") (pinfunction "S_1") (pintype "passive"))
    )
    (net (code "88") (name "Net-(K15B-P)") (class "Default")
      (node (ref "K15") (pin "3") (pinfunction "P_3") (pintype "passive"))
      (node (ref "X16") (pin "2") (pinfunction "S_2") (pintype "passive"))
    )
    (net (code "89") (name "Net-(K15B-S)") (class "Default")
      (node (ref "K15") (pin "4") (pinfunction "S_4") (pintype "passive"))
      (node (ref "X16") (pin "3") (pinfunction "S_3") (pintype "passive"))
    )
    (net (code "90") (name "Net-(K16A--)") (class "Default")
      (node (ref "D17") (pin "A") (pinfunction "A_A") (pintype "passive"))
      (node (ref "K16") (pin "8") (pinfunction "-_8") (pintype "passive"))
      (node (ref "T17") (pin "1") (pinfunction "C_1") (pintype "passive"))
    )
    (net (code "91") (name "Net-(K16B-O)") (class "Default")
      (node (ref "K16") (pin "2") (pinfunction "O_2") (pintype "passive"))
      (node (ref "X1") (pin "1") (pinfunction "S_1") (pintype "passive"))
    )
    (net (code "92") (name "Net-(K16B-P)") (class "Default")
      (node (ref "K16") (pin "3") (pinfunction "P_3") (pintype "passive"))
      (node (ref "X1") (pin "2") (pinfunction "S_2") (pintype "passive"))
    )
    (net (code "93") (name "Net-(K16B-S)") (class "Default")
      (node (ref "K16") (pin "4") (pinfunction "S_4") (pintype "passive"))
      (node (ref "X1") (pin "3") (pinfunction "S_3") (pintype "passive"))
    )
    (net (code "94") (name "Net-(T1-B)") (class "Default")
      (node (ref "R2") (pin "2") (pinfunction "2_2") (pintype "passive"))
      (node (ref "T1") (pin "3") (pinfunction "B_3") (pintype "passive"))
    )
    (net (code "95") (name "Net-(T2-B)") (class "Default")
      (node (ref "R3") (pin "2") (pinfunction "2_2") (pintype "passive"))
      (node (ref "T2") (pin "3") (pinfunction "B_3") (pintype "passive"))
    )
    (net (code "96") (name "Net-(T3-B)") (class "Default")
      (node (ref "R4") (pin "2") (pinfunction "2_2") (pintype "passive"))
      (node (ref "T3") (pin "3") (pinfunction "B_3") (pintype "passive"))
    )
    (net (code "97") (name "Net-(T4-B)") (class "Default")
      (node (ref "R5") (pin "2") (pinfunction "2_2") (pintype "passive"))
      (node (ref "T4") (pin "3") (pinfunction "B_3") (pintype "passive"))
    )
    (net (code "98") (name "Net-(T5-B)") (class "Default")
      (node (ref "R6") (pin "2") (pinfunction "2_2") (pintype "passive"))
      (node (ref "T5") (pin "3") (pinfunction "B_3") (pintype "passive"))
    )
    (net (code "99") (name "Net-(T6-B)") (class "Default")
      (node (ref "R7") (pin "2") (pinfunction "2_2") (pintype "passive"))
      (node (ref "T6") (pin "3") (pinfunction "B_3") (pintype "passive"))
    )
    (net (code "100") (name "Net-(T7-B)") (class "Default")
      (node (ref "R8") (pin "2") (pinfunction "2_2") (pintype "passive"))
      (node (ref "T7") (pin "3") (pinfunction "B_3") (pintype "passive"))
    )
    (net (code "101") (name "Net-(T8-B)") (class "Default")
      (node (ref "R9") (pin "2") (pinfunction "2_2") (pintype "passive"))
      (node (ref "T8") (pin "3") (pinfunction "B_3") (pintype "passive"))
    )
    (net (code "102") (name "Net-(T9-B)") (class "Default")
      (node (ref "R10") (pin "2") (pinfunction "2_2") (pintype "passive"))
      (node (ref "T9") (pin "3") (pinfunction "B_3") (pintype "passive"))
    )
    (net (code "103") (name "Net-(T10-B)") (class "Default")
      (node (ref "R11") (pin "2") (pinfunction "2_2") (pintype "passive"))
      (node (ref "T10") (pin "3") (pinfunction "B_3") (pintype "passive"))
    )
    (net (code "104") (name "Net-(T11-B)") (class "Default")
      (node (ref "R12") (pin "2") (pinfunction "2_2") (pintype "passive"))
      (node (ref "T11") (pin "3") (pinfunction "B_3") (pintype "passive"))
    )
    (net (code "105") (name "Net-(T12-B)") (class "Default")
      (node (ref "R13") (pin "2") (pinfunction "2_2") (pintype "passive"))
      (node (ref "T12") (pin "3") (pinfunction "B_3") (pintype "passive"))
    )
    (net (code "106") (name "Net-(T13-B)") (class "Default")
      (node (ref "R14") (pin "2") (pinfunction "2_2") (pintype "passive"))
      (node (ref "T13") (pin "3") (pinfunction "B_3") (pintype "passive"))
    )
    (net (code "107") (name "Net-(T14-B)") (class "Default")
      (node (ref "R15") (pin "2") (pinfunction "2_2") (pintype "passive"))
      (node (ref "T14") (pin "3") (pinfunction "B_3") (pintype "passive"))
    )
    (net (code "108") (name "Net-(T15-B)") (class "Default")
      (node (ref "R16") (pin "2") (pinfunction "2_2") (pintype "passive"))
      (node (ref "T15") (pin "3") (pinfunction "B_3") (pintype "passive"))
    )
    (net (code "109") (name "Net-(T17-B)") (class "Default")
      (node (ref "R1") (pin "2") (pinfunction "2_2") (pintype "passive"))
      (node (ref "T17") (pin "3") (pinfunction "B_3") (pintype "passive"))
    )
    (net (code "110") (name "unconnected-(K1C-O-Pad7)") (class "Default")
      (node (ref "K1") (pin "7") (pinfunction "O_7") (pintype "passive"))
    )
    (net (code "111") (name "unconnected-(K1C-P-Pad6)") (class "Default")
      (node (ref "K1") (pin "6") (pinfunction "P_6") (pintype "passive"))
    )
    (net (code "112") (name "unconnected-(K1C-S-Pad5)") (class "Default")
      (node (ref "K1") (pin "5") (pinfunction "S_5") (pintype "passive"))
    )
    (net (code "113") (name "unconnected-(K2C-O-Pad7)") (class "Default")
      (node (ref "K2") (pin "7") (pinfunction "O_7") (pintype "passive"))
    )
    (net (code "114") (name "unconnected-(K2C-P-Pad6)") (class "Default")
      (node (ref "K2") (pin "6") (pinfunction "P_6") (pintype "passive"))
    )
    (net (code "115") (name "unconnected-(K2C-S-Pad5)") (class "Default")
      (node (ref "K2") (pin "5") (pinfunction "S_5") (pintype "passive"))
    )
    (net (code "116") (name "unconnected-(K3C-O-Pad7)") (class "Default")
      (node (ref "K3") (pin "7") (pinfunction "O_7") (pintype "passive"))
    )
    (net (code "117") (name "unconnected-(K3C-P-Pad6)") (class "Default")
      (node (ref "K3") (pin "6") (pinfunction "P_6") (pintype "passive"))
    )
    (net (code "118") (name "unconnected-(K3C-S-Pad5)") (class "Default")
      (node (ref "K3") (pin "5") (pinfunction "S_5") (pintype "passive"))
    )
    (net (code "119") (name "unconnected-(K4C-O-Pad7)") (class "Default")
      (node (ref "K4") (pin "7") (pinfunction "O_7") (pintype "passive"))
    )
    (net (code "120") (name "unconnected-(K4C-P-Pad6)") (class "Default")
      (node (ref "K4") (pin "6") (pinfunction "P_6") (pintype "passive"))
    )
    (net (code "121") (name "unconnected-(K4C-S-Pad5)") (class "Default")
      (node (ref "K4") (pin "5") (pinfunction "S_5") (pintype "passive"))
    )
    (net (code "122") (name "unconnected-(K5C-O-Pad7)") (class "Default")
      (node (ref "K5") (pin "7") (pinfunction "O_7") (pintype "passive"))
    )
    (net (code "123") (name "unconnected-(K5C-P-Pad6)") (class "Default")
      (node (ref "K5") (pin "6") (pinfunction "P_6") (pintype "passive"))
    )
    (net (code "124") (name "unconnected-(K5C-S-Pad5)") (class "Default")
      (node (ref "K5") (pin "5") (pinfunction "S_5") (pintype "passive"))
    )
    (net (code "125") (name "unconnected-(K6C-O-Pad7)") (class "Default")
      (node (ref "K6") (pin "7") (pinfunction "O_7") (pintype "passive"))
    )
    (net (code "126") (name "unconnected-(K6C-P-Pad6)") (class "Default")
      (node (ref "K6") (pin "6") (pinfunction "P_6") (pintype "passive"))
    )
    (net (code "127") (name "unconnected-(K6C-S-Pad5)") (class "Default")
      (node (ref "K6") (pin "5") (pinfunction "S_5") (pintype "passive"))
    )
    (net (code "128") (name "unconnected-(K7C-O-Pad7)") (class "Default")
      (node (ref "K7") (pin "7") (pinfunction "O_7") (pintype "passive"))
    )
    (net (code "129") (name "unconnected-(K7C-P-Pad6)") (class "Default")
      (node (ref "K7") (pin "6") (pinfunction "P_6") (pintype "passive"))
    )
    (net (code "130") (name "unconnected-(K7C-S-Pad5)") (class "Default")
      (node (ref "K7") (pin "5") (pinfunction "S_5") (pintype "passive"))
    )
    (net (code "131") (name "unconnected-(K8C-O-Pad7)") (class "Default")
      (node (ref "K8") (pin "7") (pinfunction "O_7") (pintype "passive"))
    )
    (net (code "132") (name "unconnected-(K8C-P-Pad6)") (class "Default")
      (node (ref "K8") (pin "6") (pinfunction "P_6") (pintype "passive"))
    )
    (net (code "133") (name "unconnected-(K8C-S-Pad5)") (class "Default")
      (node (ref "K8") (pin "5") (pinfunction "S_5") (pintype "passive"))
    )
    (net (code "134") (name "unconnected-(K9C-O-Pad7)") (class "Default")
      (node (ref "K9") (pin "7") (pinfunction "O_7") (pintype "passive"))
    )
    (net (code "135") (name "unconnected-(K9C-P-Pad6)") (class "Default")
      (node (ref "K9") (pin "6") (pinfunction "P_6") (pintype "passive"))
    )
    (net (code "136") (name "unconnected-(K9C-S-Pad5)") (class "Default")
      (node (ref "K9") (pin "5") (pinfunction "S_5") (pintype "passive"))
    )
    (net (code "137") (name "unconnected-(K10C-O-Pad7)") (class "Default")
      (node (ref "K10") (pin "7") (pinfunction "O_7") (pintype "passive"))
    )
    (net (code "138") (name "unconnected-(K10C-P-Pad6)") (class "Default")
      (node (ref "K10") (pin "6") (pinfunction "P_6") (pintype "passive"))
    )
    (net (code "139") (name "unconnected-(K10C-S-Pad5)") (class "Default")
      (node (ref "K10") (pin "5") (pinfunction "S_5") (pintype "passive"))
    )
    (net (code "140") (name "unconnected-(K11C-O-Pad7)") (class "Default")
      (node (ref "K11") (pin "7") (pinfunction "O_7") (pintype "passive"))
    )
    (net (code "141") (name "unconnected-(K11C-P-Pad6)") (class "Default")
      (node (ref "K11") (pin "6") (pinfunction "P_6") (pintype "passive"))
    )
    (net (code "142") (name "unconnected-(K11C-S-Pad5)") (class "Default")
      (node (ref "K11") (pin "5") (pinfunction "S_5") (pintype "passive"))
    )
    (net (code "143") (name "unconnected-(K12C-O-Pad7)") (class "Default")
      (node (ref "K12") (pin "7") (pinfunction "O_7") (pintype "passive"))
    )
    (net (code "144") (name "unconnected-(K12C-P-Pad6)") (class "Default")
      (node (ref "K12") (pin "6") (pinfunction "P_6") (pintype "passive"))
    )
    (net (code "145") (name "unconnected-(K12C-S-Pad5)") (class "Default")
      (node (ref "K12") (pin "5") (pinfunction "S_5") (pintype "passive"))
    )
    (net (code "146") (name "unconnected-(K13C-O-Pad7)") (class "Default")
      (node (ref "K13") (pin "7") (pinfunction "O_7") (pintype "passive"))
    )
    (net (code "147") (name "unconnected-(K13C-P-Pad6)") (class "Default")
      (node (ref "K13") (pin "6") (pinfunction "P_6") (pintype "passive"))
    )
    (net (code "148") (name "unconnected-(K13C-S-Pad5)") (class "Default")
      (node (ref "K13") (pin "5") (pinfunction "S_5") (pintype "passive"))
    )
    (net (code "149") (name "unconnected-(K14C-O-Pad7)") (class "Default")
      (node (ref "K14") (pin "7") (pinfunction "O_7") (pintype "passive"))
    )
    (net (code "150") (name "unconnected-(K14C-P-Pad6)") (class "Default")
      (node (ref "K14") (pin "6") (pinfunction "P_6") (pintype "passive"))
    )
    (net (code "151") (name "unconnected-(K14C-S-Pad5)") (class "Default")
      (node (ref "K14") (pin "5") (pinfunction "S_5") (pintype "passive"))
    )
    (net (code "152") (name "unconnected-(K15C-O-Pad7)") (class "Default")
      (node (ref "K15") (pin "7") (pinfunction "O_7") (pintype "passive"))
    )
    (net (code "153") (name "unconnected-(K15C-P-Pad6)") (class "Default")
      (node (ref "K15") (pin "6") (pinfunction "P_6") (pintype "passive"))
    )
    (net (code "154") (name "unconnected-(K15C-S-Pad5)") (class "Default")
      (node (ref "K15") (pin "5") (pinfunction "S_5") (pintype "passive"))
    )
    (net (code "155") (name "unconnected-(K16C-O-Pad7)") (class "Default")
      (node (ref "K16") (pin "7") (pinfunction "O_7") (pintype "passive"))
    )
    (net (code "156") (name "unconnected-(K16C-P-Pad6)") (class "Default")
      (node (ref "K16") (pin "6") (pinfunction "P_6") (pintype "passive"))
    )
    (net (code "157") (name "unconnected-(K16C-S-Pad5)") (class "Default")
      (node (ref "K16") (pin "5") (pinfunction "S_5") (pintype "passive"))
    )
  )
)
